# EasyEDA_Source.net
KiCad netlist of a schematic drawn in EasyEDA
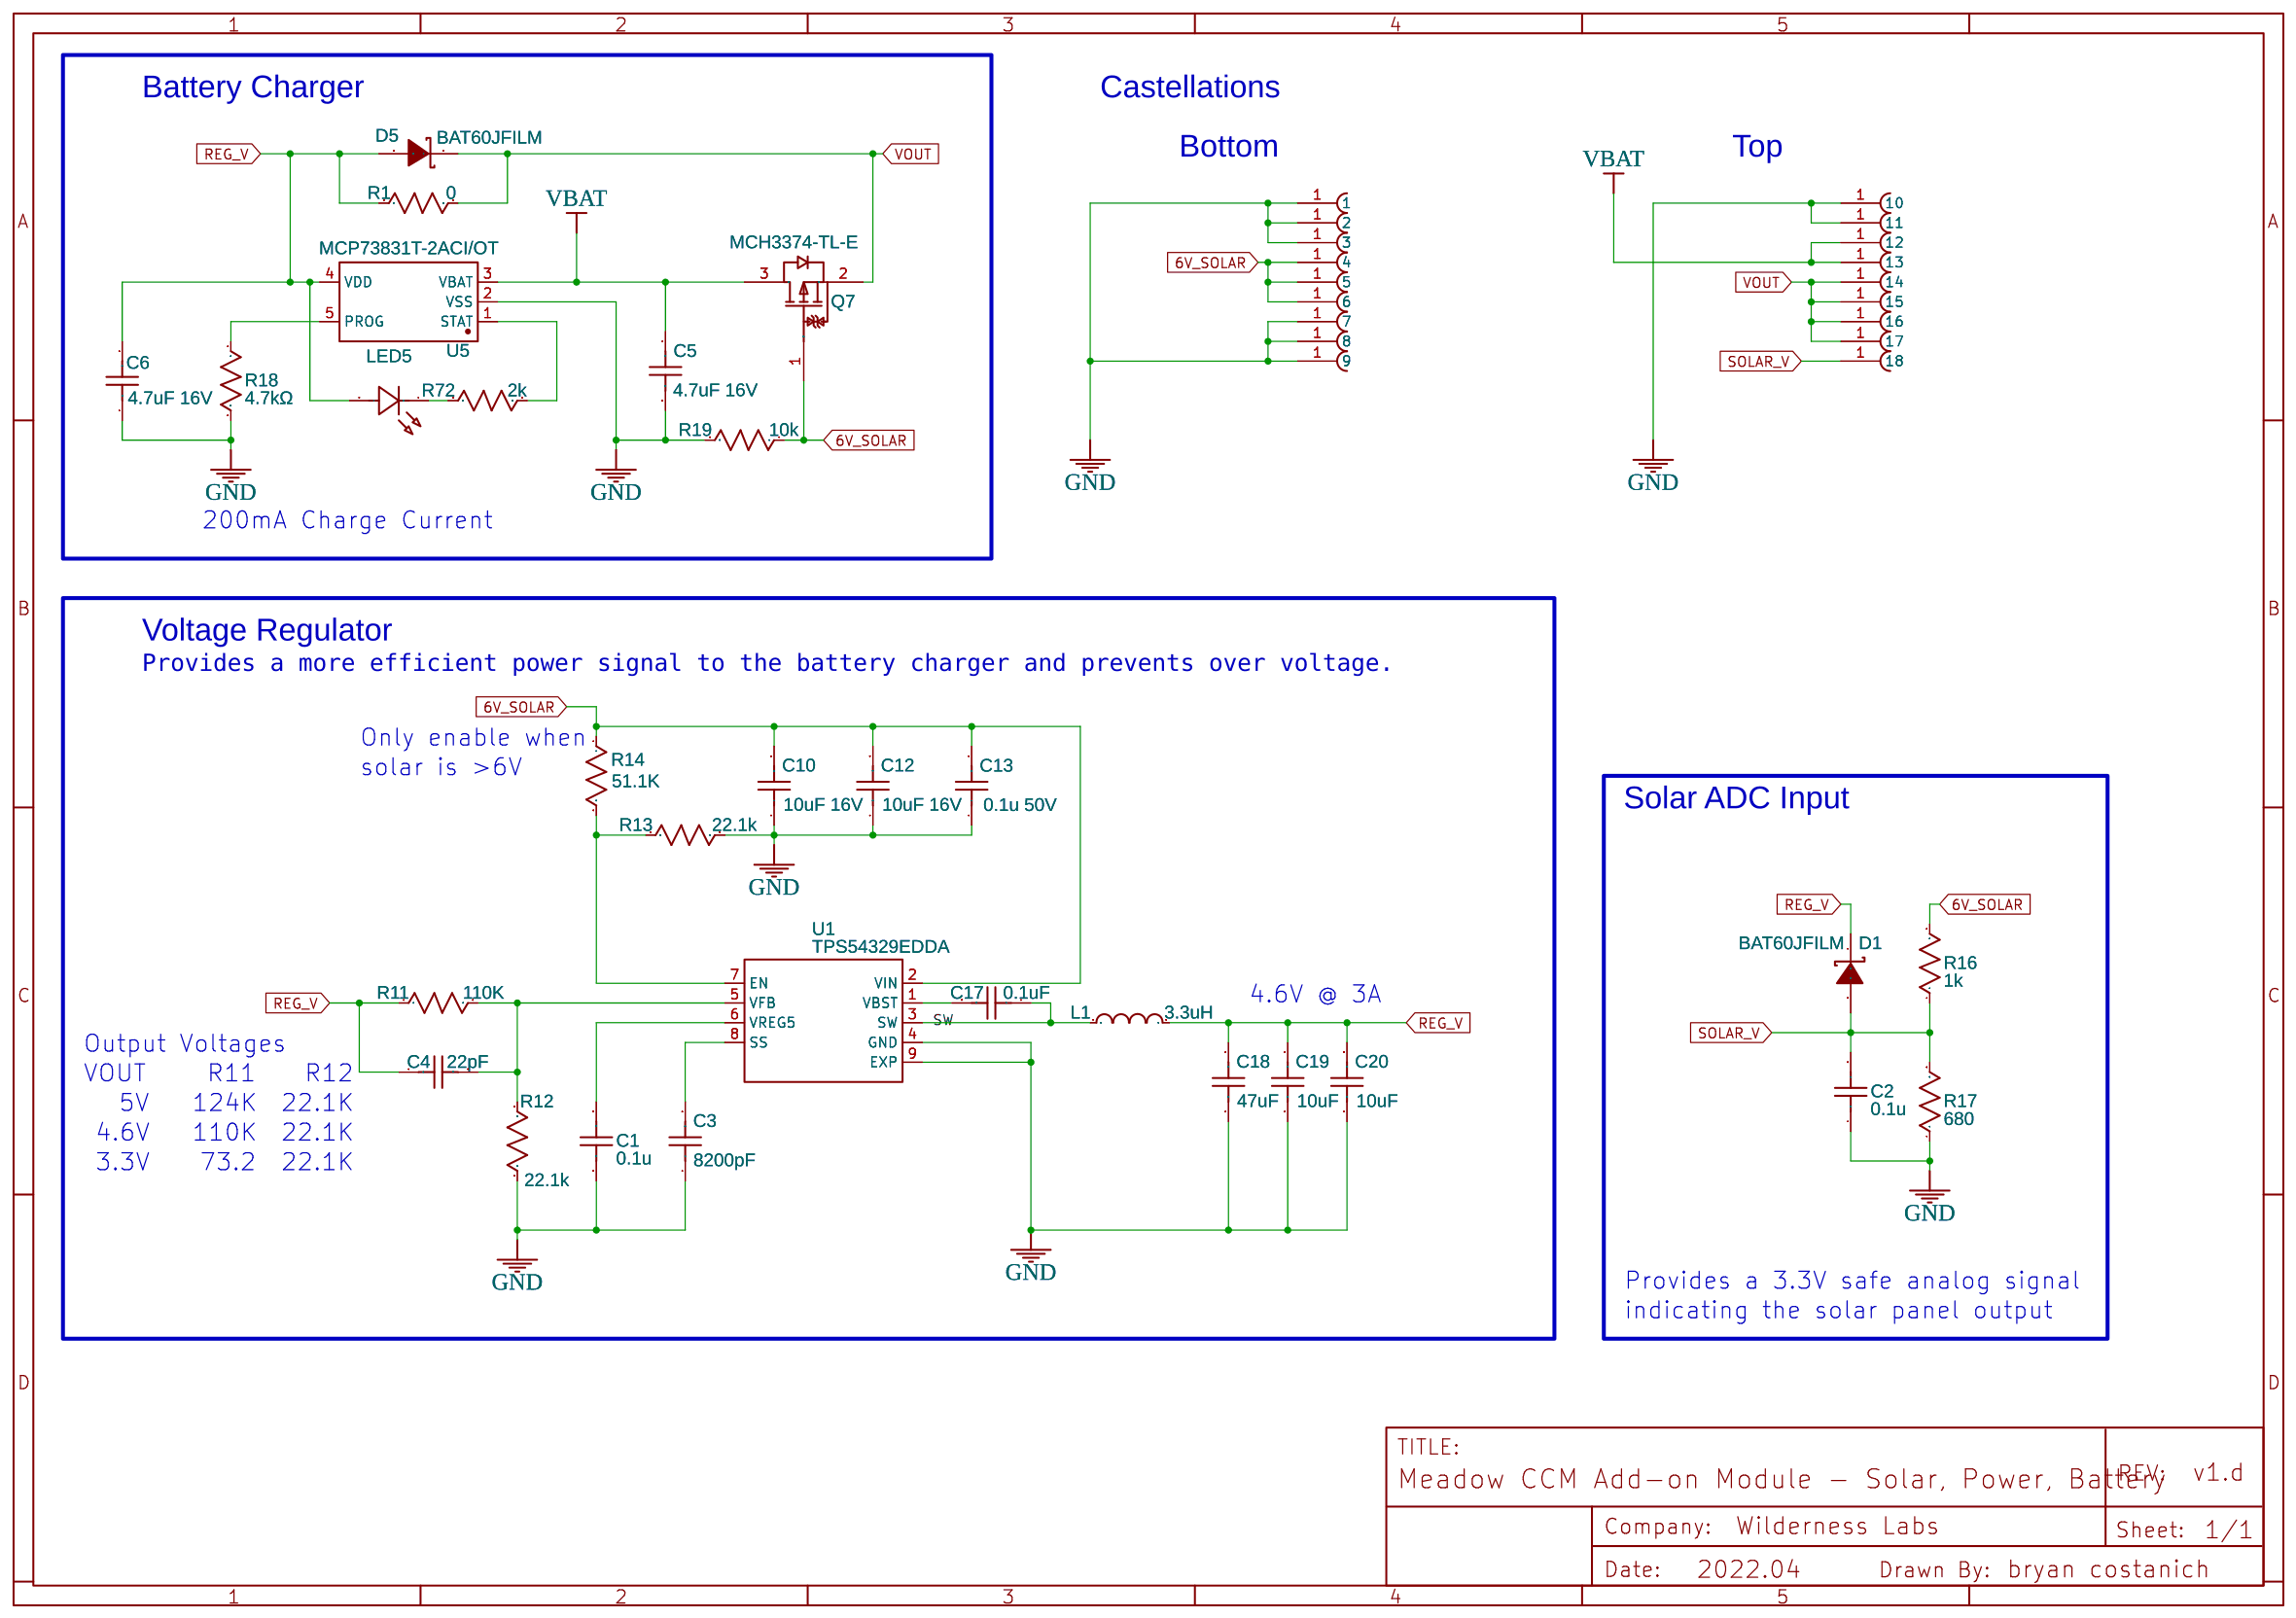
[diagram p0: schematic sheet]

(export (version "E")
  (design (tool "Eeschema 10.0.6"))
  (components
    (comp (ref "C1")
      (value "0.1u")
      (fields (field (name "BOM_Manufacturer Part") "CC0603KRX7R9BB103"))
      (libsource (lib "") (part "C_0402_US_1"))
    )
    (comp (ref "C2")
      (value "0.1u")
      (fields (field (name "BOM_Manufacturer Part") "CC0603KRX7R9BB103"))
      (libsource (lib "") (part "C_0402_US_1"))
    )
    (comp (ref "C3")
      (value "8200pF")
      (fields (field (name "BOM_Manufacturer Part") "CC0603KRX7R9BB822"))
      (libsource (lib "") (part "C_0603_US"))
    )
    (comp (ref "C4")
      (value "22pF")
      (fields (field (name "BOM_Manufacturer Part") "CC0603JRNPO9BN220"))
      (libsource (lib "") (part "C_0603_US_1"))
    )
    (comp (ref "C5")
      (value "4.7uF 16V")
      (fields (field (name "BOM_Manufacturer Part") "CC0805KKX7R7BB475"))
      (libsource (lib "") (part "C_0805_US_1"))
    )
    (comp (ref "C6")
      (value "4.7uF 16V")
      (fields (field (name "BOM_Manufacturer Part") "CC0805KKX7R7BB475"))
      (libsource (lib "") (part "C_0805_US"))
    )
    (comp (ref "C10")
      (value "10uF 16V")
      (fields (field (name "BOM_Manufacturer Part") "CC0805KRX5R7BB106"))
      (libsource (lib "") (part "C_0805_US"))
    )
    (comp (ref "C12")
      (value "10uF 16V")
      (fields (field (name "BOM_Manufacturer Part") "CC0805KRX5R7BB106"))
      (libsource (lib "") (part "C_0805_US"))
    )
    (comp (ref "C13")
      (value "0.1u 50V")
      (fields (field (name "BOM_Manufacturer Part") "CC0603KRX7R9BB103"))
      (libsource (lib "") (part "C_0402_US_1"))
    )
    (comp (ref "C17")
      (value "0.1uF")
      (fields (field (name "BOM_Manufacturer Part") "CC0603KRX7R9BB103"))
      (libsource (lib "") (part "C_0402_US"))
    )
    (comp (ref "C18")
      (value "47uF")
      (fields (field (name "BOM_Manufacturer Part") "CC1210KKX5R6BB476"))
      (libsource (lib "") (part "C_0402_US_1"))
    )
    (comp (ref "C19")
      (value "10uF")
      (fields (field (name "BOM_Manufacturer Part") "CC0805KRX5R7BB106"))
      (libsource (lib "") (part "C_0805_US"))
    )
    (comp (ref "C20")
      (value "10uF")
      (fields (field (name "BOM_Manufacturer Part") "CC0805KRX5R7BB106"))
      (libsource (lib "") (part "C_0805_US"))
    )
    (comp (ref "D1")
      (value "BAT60JFILM")
      (fields (field (name "BOM_Supplier Part") "C133103"))
      (libsource (lib "") (part "BAT60JFILM"))
    )
    (comp (ref "D5")
      (value "BAT60JFILM")
      (fields (field (name "BOM_Supplier Part") "C133103"))
      (libsource (lib "") (part "BAT60JFILM_1"))
    )
    (comp (ref "L1")
      (value "3.3uH")
      (fields
        (field (name "BOM_Manufacturer Part") "NRS5040T3R3NMGJ")
        (field (name "BOM_Supplier Part") "C222946")
      )
      (libsource (lib "") (part "NRS5040T3R3NMGJ"))
    )
    (comp (ref "LED5") (value "EAST1608GA0") (libsource (lib "") (part "EAST1608GA0")))
    (comp (ref "Q7") (value "MCH3374-TL-E") (libsource (lib "") (part "MCH3374-TL-E")))
    (comp (ref "R1")
      (value "0")
      (fields (field (name "BOM_Manufacturer Part") "RC0603JR-070RL"))
      (libsource (lib "") (part "R_0603_US"))
    )
    (comp (ref "R11")
      (value "110K")
      (fields (field (name "BOM_Manufacturer Part") "RC0603FR-07110KL"))
      (libsource (lib "") (part "R_0603_US"))
    )
    (comp (ref "R12")
      (value "22.1k")
      (fields (field (name "BOM_Manufacturer Part") "RC0603FR-0722K1L"))
      (libsource (lib "") (part "R_0603_US_2"))
    )
    (comp (ref "R13")
      (value "22.1k")
      (fields (field (name "BOM_Manufacturer Part") "RC0603FR-0722K1L"))
      (libsource (lib "") (part "R_0603_US_1"))
    )
    (comp (ref "R14")
      (value "51.1K")
      (fields (field (name "BOM_Manufacturer Part") "RC0603FR-0751K1L"))
      (libsource (lib "") (part "R_0603_US_3"))
    )
    (comp (ref "R16")
      (value "1k")
      (fields (field (name "BOM_Manufacturer Part") "RC0603FR-071KL"))
      (libsource (lib "") (part "R_0402_US"))
    )
    (comp (ref "R17")
      (value "680")
      (fields (field (name "BOM_Manufacturer Part") "RC0603FR-07680RL"))
      (libsource (lib "") (part "R_0402_US"))
    )
    (comp (ref "R18")
      (value "4.7kΩ")
      (fields (field (name "BOM_Manufacturer Part") "RC0603FR-074K7L"))
      (libsource (lib "") (part "Res_0603(1/10W)_US"))
    )
    (comp (ref "R19")
      (value "10k")
      (fields (field (name "BOM_Manufacturer Part") "RC0603FR-0710KL"))
      (libsource (lib "") (part "R_0402_US_1"))
    )
    (comp (ref "R72")
      (value "2k")
      (fields (field (name "BOM_Manufacturer Part") "RC0603FR-072KL"))
      (libsource (lib "") (part "R_0603_US"))
    )
    (comp (ref "U1")
      (value "TPS54329EDDA")
      (fields (field (name "BOM_Supplier Part") "C38344"))
      (libsource (lib "") (part "TPS54329EDDAR LOGICAL"))
    )
    (comp (ref "U2") (value "1.5MM SMT CASTELLATION") (libsource (lib "") (part "1.5MM SMT CASTELLATION_13")))
    (comp (ref "U3") (value "1.5MM SMT CASTELLATION") (libsource (lib "") (part "1.5MM SMT CASTELLATION_3")))
    (comp (ref "U4") (value "1.5MM SMT CASTELLATION") (libsource (lib "") (part "1.5MM SMT CASTELLATION_11")))
    (comp (ref "U5")
      (value "MCP73831T-2ACI/OT")
      (fields (field (name "BOM_Supplier Part") "C424093"))
      (libsource (lib "") (part "MCP73831T-2ACI/OT"))
    )
    (comp (ref "U6") (value "1.5MM SMT CASTELLATION") (libsource (lib "") (part "1.5MM SMT CASTELLATION_16")))
    (comp (ref "U7") (value "1.5MM SMT CASTELLATION") (libsource (lib "") (part "1.5MM SMT CASTELLATION_17")))
    (comp (ref "U8") (value "1.5MM SMT CASTELLATION") (libsource (lib "") (part "1.5MM SMT CASTELLATION_7")))
    (comp (ref "U9") (value "1.5MM SMT CASTELLATION") (libsource (lib "") (part "1.5MM SMT CASTELLATION_8")))
    (comp (ref "U10") (value "1.5MM SMT CASTELLATION") (libsource (lib "") (part "1.5MM SMT CASTELLATION_9")))
    (comp (ref "U19")
      (value "1.5MM SMT CASTELLATION")
      (libsource (lib "") (part "1.5MM SMT CASTELLATION_10"))
    )
    (comp (ref "U20") (value "1.5MM SMT CASTELLATION") (libsource (lib "") (part "1.5MM SMT CASTELLATION_2")))
    (comp (ref "U28") (value "1.5MM SMT CASTELLATION") (libsource (lib "") (part "1.5MM SMT CASTELLATION_6")))
    (comp (ref "U29")
      (value "1.5MM SMT CASTELLATION")
      (libsource (lib "") (part "1.5MM SMT CASTELLATION_12"))
    )
    (comp (ref "U32") (value "1.5MM SMT CASTELLATION") (libsource (lib "") (part "1.5MM SMT CASTELLATION_5")))
    (comp (ref "U33") (value "1.5MM SMT CASTELLATION") (libsource (lib "") (part "1.5MM SMT CASTELLATION")))
    (comp (ref "U34") (value "1.5MM SMT CASTELLATION") (libsource (lib "") (part "1.5MM SMT CASTELLATION_1")))
    (comp (ref "U35")
      (value "1.5MM SMT CASTELLATION")
      (libsource (lib "") (part "1.5MM SMT CASTELLATION_14"))
    )
    (comp (ref "U36") (value "1.5MM SMT CASTELLATION") (libsource (lib "") (part "1.5MM SMT CASTELLATION_4")))
    (comp (ref "U37")
      (value "1.5MM SMT CASTELLATION")
      (libsource (lib "") (part "1.5MM SMT CASTELLATION_15"))
    )
  )
  (nets
    (net (code "1") (name "/SW") (class "Default")
      (node (ref "C17") (pin "1") (pinfunction "1_1") (pintype "unspecified"))
      (node (ref "L1") (pin "1") (pinfunction "1_1") (pintype "unspecified"))
      (node (ref "U1") (pin "3") (pinfunction "SW_3") (pintype "unspecified"))
    )
    (net (code "2") (name "6V_SOLAR") (class "Default")
      (node (ref "C10") (pin "2") (pinfunction "2_2") (pintype "unspecified"))
      (node (ref "C12") (pin "2") (pinfunction "2_2") (pintype "unspecified"))
      (node (ref "C13") (pin "2") (pinfunction "2_2") (pintype "unspecified"))
      (node (ref "Q7") (pin "1") (pinfunction "G_1") (pintype "unspecified"))
      (node (ref "R14") (pin "1") (pinfunction "1_1") (pintype "unspecified"))
      (node (ref "R16") (pin "2") (pinfunction "2_2") (pintype "unspecified"))
      (node (ref "R19") (pin "1") (pinfunction "1_1") (pintype "unspecified"))
      (node (ref "U1") (pin "2") (pinfunction "VIN_2") (pintype "unspecified"))
      (node (ref "U32") (pin "1") (pinfunction "6_1") (pintype "unspecified"))
      (node (ref "U33") (pin "1") (pinfunction "5_1") (pintype "unspecified"))
      (node (ref "U34") (pin "1") (pinfunction "4_1") (pintype "unspecified"))
    )
    (net (code "3") (name "GND") (class "Default")
      (node (ref "C1") (pin "1") (pinfunction "1_1") (pintype "unspecified"))
      (node (ref "C10") (pin "1") (pinfunction "1_1") (pintype "unspecified"))
      (node (ref "C12") (pin "1") (pinfunction "1_1") (pintype "unspecified"))
      (node (ref "C13") (pin "1") (pinfunction "1_1") (pintype "unspecified"))
      (node (ref "C18") (pin "1") (pinfunction "1_1") (pintype "unspecified"))
      (node (ref "C19") (pin "1") (pinfunction "1_1") (pintype "unspecified"))
      (node (ref "C2") (pin "1") (pinfunction "1_1") (pintype "unspecified"))
      (node (ref "C20") (pin "1") (pinfunction "1_1") (pintype "unspecified"))
      (node (ref "C3") (pin "1") (pinfunction "1_1") (pintype "unspecified"))
      (node (ref "C5") (pin "2") (pinfunction "2_2") (pintype "unspecified"))
      (node (ref "C6") (pin "1") (pinfunction "1_1") (pintype "unspecified"))
      (node (ref "R12") (pin "1") (pinfunction "1_1") (pintype "unspecified"))
      (node (ref "R13") (pin "1") (pinfunction "1_1") (pintype "unspecified"))
      (node (ref "R17") (pin "1") (pinfunction "1_1") (pintype "unspecified"))
      (node (ref "R18") (pin "2") (pinfunction "2_2") (pintype "unspecified"))
      (node (ref "R19") (pin "2") (pinfunction "2_2") (pintype "unspecified"))
      (node (ref "U1") (pin "4") (pinfunction "GND_4") (pintype "unspecified"))
      (node (ref "U1") (pin "9") (pinfunction "EXP_9") (pintype "unspecified"))
      (node (ref "U19") (pin "1") (pinfunction "8_1") (pintype "unspecified"))
      (node (ref "U20") (pin "1") (pinfunction "9_1") (pintype "unspecified"))
      (node (ref "U28") (pin "1") (pinfunction "10_1") (pintype "unspecified"))
      (node (ref "U29") (pin "1") (pinfunction "11_1") (pintype "unspecified"))
      (node (ref "U3") (pin "1") (pinfunction "7_1") (pintype "unspecified"))
      (node (ref "U35") (pin "1") (pinfunction "1_1") (pintype "unspecified"))
      (node (ref "U36") (pin "1") (pinfunction "2_1") (pintype "unspecified"))
      (node (ref "U37") (pin "1") (pinfunction "3_1") (pintype "unspecified"))
      (node (ref "U5") (pin "2") (pinfunction "VSS_2") (pintype "unspecified"))
    )
    (net (code "4") (name "Net-(LED5-K)") (class "Default")
      (node (ref "LED5") (pin "1") (pinfunction "K_1") (pintype "unspecified"))
      (node (ref "R72") (pin "1") (pinfunction "1_1") (pintype "unspecified"))
    )
    (net (code "5") (name "Net-(U1-EN)") (class "Default")
      (node (ref "R13") (pin "2") (pinfunction "2_2") (pintype "unspecified"))
      (node (ref "R14") (pin "2") (pinfunction "2_2") (pintype "unspecified"))
      (node (ref "U1") (pin "7") (pinfunction "EN_7") (pintype "unspecified"))
    )
    (net (code "6") (name "Net-(U1-SS)") (class "Default")
      (node (ref "C3") (pin "2") (pinfunction "2_2") (pintype "unspecified"))
      (node (ref "U1") (pin "8") (pinfunction "SS_8") (pintype "unspecified"))
    )
    (net (code "7") (name "Net-(U1-VBST)") (class "Default")
      (node (ref "C17") (pin "2") (pinfunction "2_2") (pintype "unspecified"))
      (node (ref "U1") (pin "1") (pinfunction "VBST_1") (pintype "unspecified"))
    )
    (net (code "8") (name "Net-(U1-VFB)") (class "Default")
      (node (ref "C4") (pin "2") (pinfunction "2_2") (pintype "unspecified"))
      (node (ref "R11") (pin "2") (pinfunction "2_2") (pintype "unspecified"))
      (node (ref "R12") (pin "2") (pinfunction "2_2") (pintype "unspecified"))
      (node (ref "U1") (pin "5") (pinfunction "VFB_5") (pintype "unspecified"))
    )
    (net (code "9") (name "Net-(U1-VREG5)") (class "Default")
      (node (ref "C1") (pin "2") (pinfunction "2_2") (pintype "unspecified"))
      (node (ref "U1") (pin "6") (pinfunction "VREG5_6") (pintype "unspecified"))
    )
    (net (code "10") (name "Net-(U5-PROG)") (class "Default")
      (node (ref "R18") (pin "1") (pinfunction "1_1") (pintype "unspecified"))
      (node (ref "U5") (pin "5") (pinfunction "PROG_5") (pintype "unspecified"))
    )
    (net (code "11") (name "Net-(U5-STAT)") (class "Default")
      (node (ref "R72") (pin "2") (pinfunction "2_2") (pintype "unspecified"))
      (node (ref "U5") (pin "1") (pinfunction "STAT_1") (pintype "unspecified"))
    )
    (net (code "12") (name "REG_V") (class "Default")
      (node (ref "C18") (pin "2") (pinfunction "2_2") (pintype "unspecified"))
      (node (ref "C19") (pin "2") (pinfunction "2_2") (pintype "unspecified"))
      (node (ref "C20") (pin "2") (pinfunction "2_2") (pintype "unspecified"))
      (node (ref "C4") (pin "1") (pinfunction "1_1") (pintype "unspecified"))
      (node (ref "C6") (pin "2") (pinfunction "2_2") (pintype "unspecified"))
      (node (ref "D1") (pin "1") (pinfunction "K_1") (pintype "unspecified"))
      (node (ref "D5") (pin "2") (pinfunction "A_2") (pintype "unspecified"))
      (node (ref "L1") (pin "2") (pinfunction "2_2") (pintype "unspecified"))
      (node (ref "LED5") (pin "2") (pinfunction "A_2") (pintype "unspecified"))
      (node (ref "R1") (pin "1") (pinfunction "1_1") (pintype "unspecified"))
      (node (ref "R11") (pin "1") (pinfunction "1_1") (pintype "unspecified"))
      (node (ref "U5") (pin "4") (pinfunction "VDD_4") (pintype "unspecified"))
    )
    (net (code "13") (name "SOLAR_V") (class "Default")
      (node (ref "C2") (pin "2") (pinfunction "2_2") (pintype "unspecified"))
      (node (ref "D1") (pin "2") (pinfunction "A_2") (pintype "unspecified"))
      (node (ref "R16") (pin "1") (pinfunction "1_1") (pintype "unspecified"))
      (node (ref "R17") (pin "2") (pinfunction "2_2") (pintype "unspecified"))
      (node (ref "U6") (pin "1") (pinfunction "18_1") (pintype "unspecified"))
    )
    (net (code "14") (name "VBAT") (class "Default")
      (node (ref "C5") (pin "1") (pinfunction "1_1") (pintype "unspecified"))
      (node (ref "Q7") (pin "3") (pinfunction "D_3") (pintype "unspecified"))
      (node (ref "U2") (pin "1") (pinfunction "12_1") (pintype "unspecified"))
      (node (ref "U5") (pin "3") (pinfunction "VBAT_3") (pintype "unspecified"))
      (node (ref "U9") (pin "1") (pinfunction "13_1") (pintype "unspecified"))
    )
    (net (code "15") (name "VOUT") (class "Default")
      (node (ref "D5") (pin "1") (pinfunction "K_1") (pintype "unspecified"))
      (node (ref "Q7") (pin "2") (pinfunction "S_2") (pintype "unspecified"))
      (node (ref "R1") (pin "2") (pinfunction "2_2") (pintype "unspecified"))
      (node (ref "U10") (pin "1") (pinfunction "14_1") (pintype "unspecified"))
      (node (ref "U4") (pin "1") (pinfunction "17_1") (pintype "unspecified"))
      (node (ref "U7") (pin "1") (pinfunction "15_1") (pintype "unspecified"))
      (node (ref "U8") (pin "1") (pinfunction "16_1") (pintype "unspecified"))
    )
  )
)
